# Yung_Chicklet.net
KiCad netlist of a schematic drawn in EAGLE
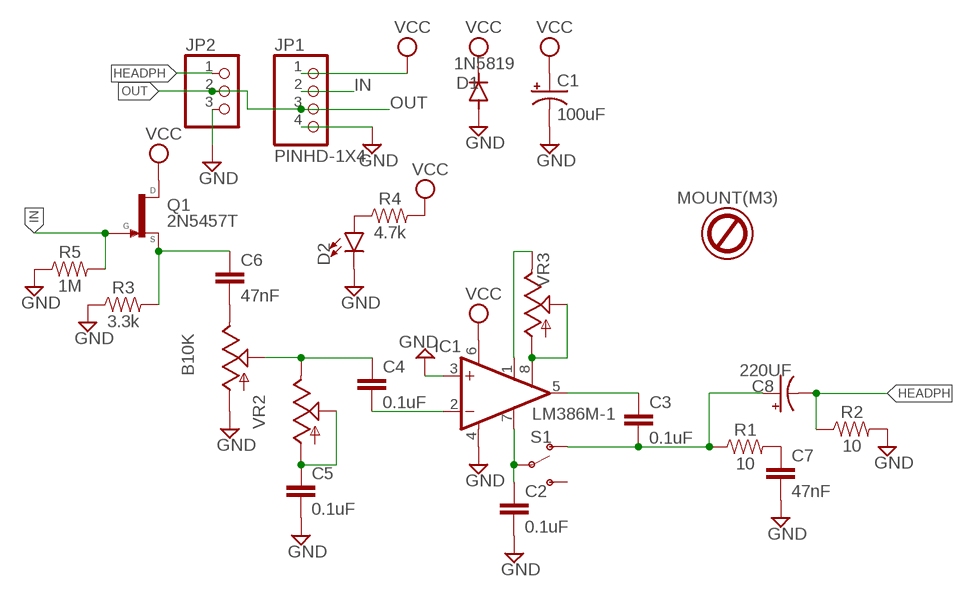
[diagram p0: schematic, sheet 1]

(export (version "E")
  (design (tool "Eeschema 10.0.6"))
  (components
    (comp (ref "B10K")
      (value "9MM_SNAP-IN_POT_")
      (footprint "eagle-import:9MM_SNAP-IN_POT")
      (libsource (lib "eagle-import") (part "9MM_SNAP-IN_POT_"))
    )
    (comp (ref "C1")
      (value "100uF")
      (footprint "eagle-import:PAN_B_SMD+THRU")
      (libsource (lib "eagle-import") (part "CAP_SMD+THRUPAN_B"))
    )
    (comp (ref "C2")
      (value "0.1uF")
      (footprint "eagle-import:0603")
      (libsource (lib "eagle-import") (part "0.1UF-0603-25V-(+80/-20%)"))
    )
    (comp (ref "C3")
      (value "0.1uF")
      (footprint "eagle-import:0603")
      (libsource (lib "eagle-import") (part "0.1UF-0603-25V-(+80/-20%)"))
    )
    (comp (ref "C4")
      (value "0.1uF")
      (footprint "eagle-import:0603")
      (libsource (lib "eagle-import") (part "0.1UF-0603-25V-(+80/-20%)"))
    )
    (comp (ref "C5")
      (value "0.1uF")
      (footprint "eagle-import:0603")
      (libsource (lib "eagle-import") (part "0.1UF-0603-25V-(+80/-20%)"))
    )
    (comp (ref "C6")
      (value "47nF")
      (footprint "eagle-import:0603")
      (libsource (lib "eagle-import") (part "47NF-0603-25V-5%"))
    )
    (comp (ref "C7")
      (value "47nF")
      (footprint "eagle-import:0603")
      (libsource (lib "eagle-import") (part "47NF-0603-25V-5%"))
    )
    (comp (ref "C8")
      (value "220UF")
      (footprint "eagle-import:PAN_B_SMD+THRU")
      (libsource (lib "eagle-import") (part "CAP_SMD+THRUPAN_B"))
    )
    (comp (ref "D1")
      (value "1N5819")
      (footprint "eagle-import:SOD123")
      (libsource (lib "eagle-import") (part "DIODE-SOD123"))
    )
    (comp (ref "D2")
      (value "LED1206")
      (footprint "eagle-import:LED-1206")
      (libsource (lib "eagle-import") (part "LED1206"))
    )
    (comp (ref "IC1")
      (value "LM386M-1")
      (footprint "eagle-import:SO08")
      (libsource (lib "eagle-import") (part "LM386?-M1"))
    )
    (comp (ref "JP1")
      (value "PINHD-1X4")
      (footprint "eagle-import:1X04")
      (libsource (lib "eagle-import") (part "PINHD-1X4"))
    )
    (comp (ref "JP2")
      (value "PINHD-1X3")
      (footprint "eagle-import:1X03")
      (libsource (lib "eagle-import") (part "PINHD-1X3"))
    )
    (comp (ref "O2")
      (value "MOUNT(M3)")
      (footprint "eagle-import:HOLE-3.5MM")
      (libsource (lib "eagle-import") (part "MOUNT(?)M3"))
    )
    (comp (ref "Q1")
      (value "2N5457T")
      (footprint "eagle-import:TO92F")
      (libsource (lib "eagle-import") (part "2N5457T"))
    )
    (comp (ref "R1")
      (value "10")
      (footprint "eagle-import:0603")
      (libsource (lib "eagle-import") (part "10OHM-0603-1/10W-1%"))
    )
    (comp (ref "R2")
      (value "10")
      (footprint "eagle-import:0603")
      (libsource (lib "eagle-import") (part "10OHM-0603-1/10W-1%"))
    )
    (comp (ref "R3")
      (value "3.3k")
      (footprint "eagle-import:0603")
      (libsource (lib "eagle-import") (part "3.3KOHM-0603-1/10W-1%"))
    )
    (comp (ref "R4")
      (value "4.7k")
      (footprint "eagle-import:0603")
      (libsource (lib "eagle-import") (part "4.7KOHM-0603-1/10W-1%"))
    )
    (comp (ref "R5")
      (value "1M")
      (footprint "eagle-import:0603")
      (libsource (lib "eagle-import") (part "1MOHM-0603-1/4W-5%"))
    )
    (comp (ref "S1")
      (value "SWITCH-SPDT-PTH-11.6X4.0MM-LOCK")
      (footprint "eagle-import:SWITCH_SPDT_PTH_11.6X4.0MM_LOCK")
      (libsource (lib "eagle-import") (part "SWITCH-SPDT-PTH-11.6X4.0MM-LOCK"))
    )
    (comp (ref "VR2")
      (value "9MM_SNAP-IN_POT_")
      (footprint "eagle-import:9MM_SNAP-IN_POT")
      (libsource (lib "eagle-import") (part "9MM_SNAP-IN_POT_"))
    )
    (comp (ref "VR3")
      (value "9MM_SNAP-IN_POT_")
      (footprint "eagle-import:9MM_SNAP-IN_POT")
      (libsource (lib "eagle-import") (part "9MM_SNAP-IN_POT_"))
    )
  )
  (nets
    (net (code "1") (name "GND") (class "Default")
      (node (ref "B10K") (pin "1") (pinfunction "A_1") (pintype "passive"))
      (node (ref "C1") (pin "-") (pinfunction "-_-") (pintype "passive"))
      (node (ref "C1") (pin "--") (pinfunction "-_--") (pintype "passive"))
      (node (ref "C2") (pin "2") (pinfunction "2_2") (pintype "passive"))
      (node (ref "C5") (pin "2") (pinfunction "2_2") (pintype "passive"))
      (node (ref "C7") (pin "2") (pinfunction "2_2") (pintype "passive"))
      (node (ref "D1") (pin "A") (pinfunction "A_A") (pintype "passive"))
      (node (ref "D2") (pin "C") (pinfunction "C_C") (pintype "passive"))
      (node (ref "IC1") (pin "3") (pinfunction "+IN_3") (pintype "input"))
      (node (ref "IC1") (pin "4") (pinfunction "GND_4") (pintype "power_in"))
      (node (ref "JP1") (pin "4") (pinfunction "4_4") (pintype "passive"))
      (node (ref "JP2") (pin "3") (pinfunction "3_3") (pintype "passive"))
      (node (ref "R2") (pin "2") (pinfunction "2_2") (pintype "passive"))
      (node (ref "R3") (pin "1") (pinfunction "1_1") (pintype "passive"))
      (node (ref "R5") (pin "1") (pinfunction "1_1") (pintype "passive"))
    )
    (net (code "2") (name "HEADPH") (class "Default")
      (node (ref "C8") (pin "-") (pinfunction "-_-") (pintype "passive"))
      (node (ref "C8") (pin "--") (pinfunction "-_--") (pintype "passive"))
      (node (ref "JP2") (pin "1") (pinfunction "1_1") (pintype "passive"))
      (node (ref "R2") (pin "1") (pinfunction "1_1") (pintype "passive"))
    )
    (net (code "3") (name "IN") (class "Default")
      (node (ref "JP1") (pin "2") (pinfunction "2_2") (pintype "passive"))
      (node (ref "Q1") (pin "1") (pinfunction "G_1") (pintype "passive"))
      (node (ref "R5") (pin "2") (pinfunction "2_2") (pintype "passive"))
    )
    (net (code "4") (name "Net-(B10K-E)") (class "Default")
      (node (ref "B10K") (pin "3") (pinfunction "E_3") (pintype "passive"))
      (node (ref "C6") (pin "2") (pinfunction "2_2") (pintype "passive"))
    )
    (net (code "5") (name "Net-(B10K-S)") (class "Default")
      (node (ref "B10K") (pin "2") (pinfunction "S_2") (pintype "passive"))
      (node (ref "C4") (pin "1") (pinfunction "1_1") (pintype "passive"))
      (node (ref "VR2") (pin "3") (pinfunction "E_3") (pintype "passive"))
    )
    (net (code "6") (name "Net-(C7-Pad1)") (class "Default")
      (node (ref "C7") (pin "1") (pinfunction "1_1") (pintype "passive"))
      (node (ref "R1") (pin "2") (pinfunction "2_2") (pintype "passive"))
    )
    (net (code "7") (name "Net-(D2-PadA)") (class "Default")
      (node (ref "D2") (pin "A") (pinfunction "A_A") (pintype "passive"))
      (node (ref "R4") (pin "1") (pinfunction "1_1") (pintype "passive"))
    )
    (net (code "8") (name "Net-(IC1--IN)") (class "Default")
      (node (ref "C4") (pin "2") (pinfunction "2_2") (pintype "passive"))
      (node (ref "IC1") (pin "2") (pinfunction "-IN_2") (pintype "input"))
    )
    (net (code "9") (name "Net-(IC1-BYPASS)") (class "Default")
      (node (ref "C2") (pin "1") (pinfunction "1_1") (pintype "passive"))
      (node (ref "IC1") (pin "7") (pinfunction "BYPASS_7") (pintype "passive"))
      (node (ref "S1") (pin "2") (pinfunction "P_2") (pintype "passive"))
    )
    (net (code "10") (name "Net-(IC1-OUT)") (class "Default")
      (node (ref "C3") (pin "1") (pinfunction "1_1") (pintype "passive"))
      (node (ref "IC1") (pin "5") (pinfunction "OUT_5") (pintype "output"))
    )
    (net (code "11") (name "Net-(Q1-S)") (class "Default")
      (node (ref "C6") (pin "1") (pinfunction "1_1") (pintype "passive"))
      (node (ref "Q1") (pin "2") (pinfunction "S_2") (pintype "passive"))
      (node (ref "R3") (pin "2") (pinfunction "2_2") (pintype "passive"))
    )
    (net (code "12") (name "Net-(S1-O)") (class "Default")
      (node (ref "C3") (pin "2") (pinfunction "2_2") (pintype "passive"))
      (node (ref "C8") (pin "+") (pinfunction "+_+") (pintype "passive"))
      (node (ref "C8") (pin "++") (pinfunction "+_++") (pintype "passive"))
      (node (ref "R1") (pin "1") (pinfunction "1_1") (pintype "passive"))
      (node (ref "S1") (pin "1") (pinfunction "O_1") (pintype "passive"))
    )
    (net (code "13") (name "Net-(VR2-A)") (class "Default")
      (node (ref "C5") (pin "1") (pinfunction "1_1") (pintype "passive"))
      (node (ref "VR2") (pin "1") (pinfunction "A_1") (pintype "passive"))
      (node (ref "VR2") (pin "2") (pinfunction "S_2") (pintype "passive"))
    )
    (net (code "14") (name "Net-(VR3-A)") (class "Default")
      (node (ref "IC1") (pin "8") (pinfunction "GAIN_8") (pintype "passive"))
      (node (ref "VR3") (pin "1") (pinfunction "A_1") (pintype "passive"))
      (node (ref "VR3") (pin "2") (pinfunction "S_2") (pintype "passive"))
    )
    (net (code "15") (name "Net-(VR3-E)") (class "Default")
      (node (ref "IC1") (pin "1") (pinfunction "GAIN_1") (pintype "passive"))
      (node (ref "VR3") (pin "3") (pinfunction "E_3") (pintype "passive"))
    )
    (net (code "16") (name "OUT") (class "Default")
      (node (ref "JP1") (pin "3") (pinfunction "3_3") (pintype "passive"))
      (node (ref "JP2") (pin "2") (pinfunction "2_2") (pintype "passive"))
    )
    (net (code "17") (name "VCC") (class "Default")
      (node (ref "C1") (pin "+") (pinfunction "+_+") (pintype "passive"))
      (node (ref "C1") (pin "++") (pinfunction "+_++") (pintype "passive"))
      (node (ref "D1") (pin "C") (pinfunction "C_C") (pintype "passive"))
      (node (ref "IC1") (pin "6") (pinfunction "VS_6") (pintype "power_in"))
      (node (ref "JP1") (pin "1") (pinfunction "1_1") (pintype "passive"))
      (node (ref "Q1") (pin "3") (pinfunction "D_3") (pintype "passive"))
      (node (ref "R4") (pin "2") (pinfunction "2_2") (pintype "passive"))
    )
    (net (code "18") (name "unconnected-(O2-P$1-PadMNT)") (class "Default")
      (node (ref "O2") (pin "MNT") (pinfunction "P$1_MNT") (pintype "bidirectional"))
    )
    (net (code "19") (name "unconnected-(S1-S-Pad3)") (class "Default")
      (node (ref "S1") (pin "3") (pinfunction "S_3") (pintype "passive"))
    )
  )
)
